# pmi_extension_2k13.net
KiCad netlist of a schematic drawn in EAGLE
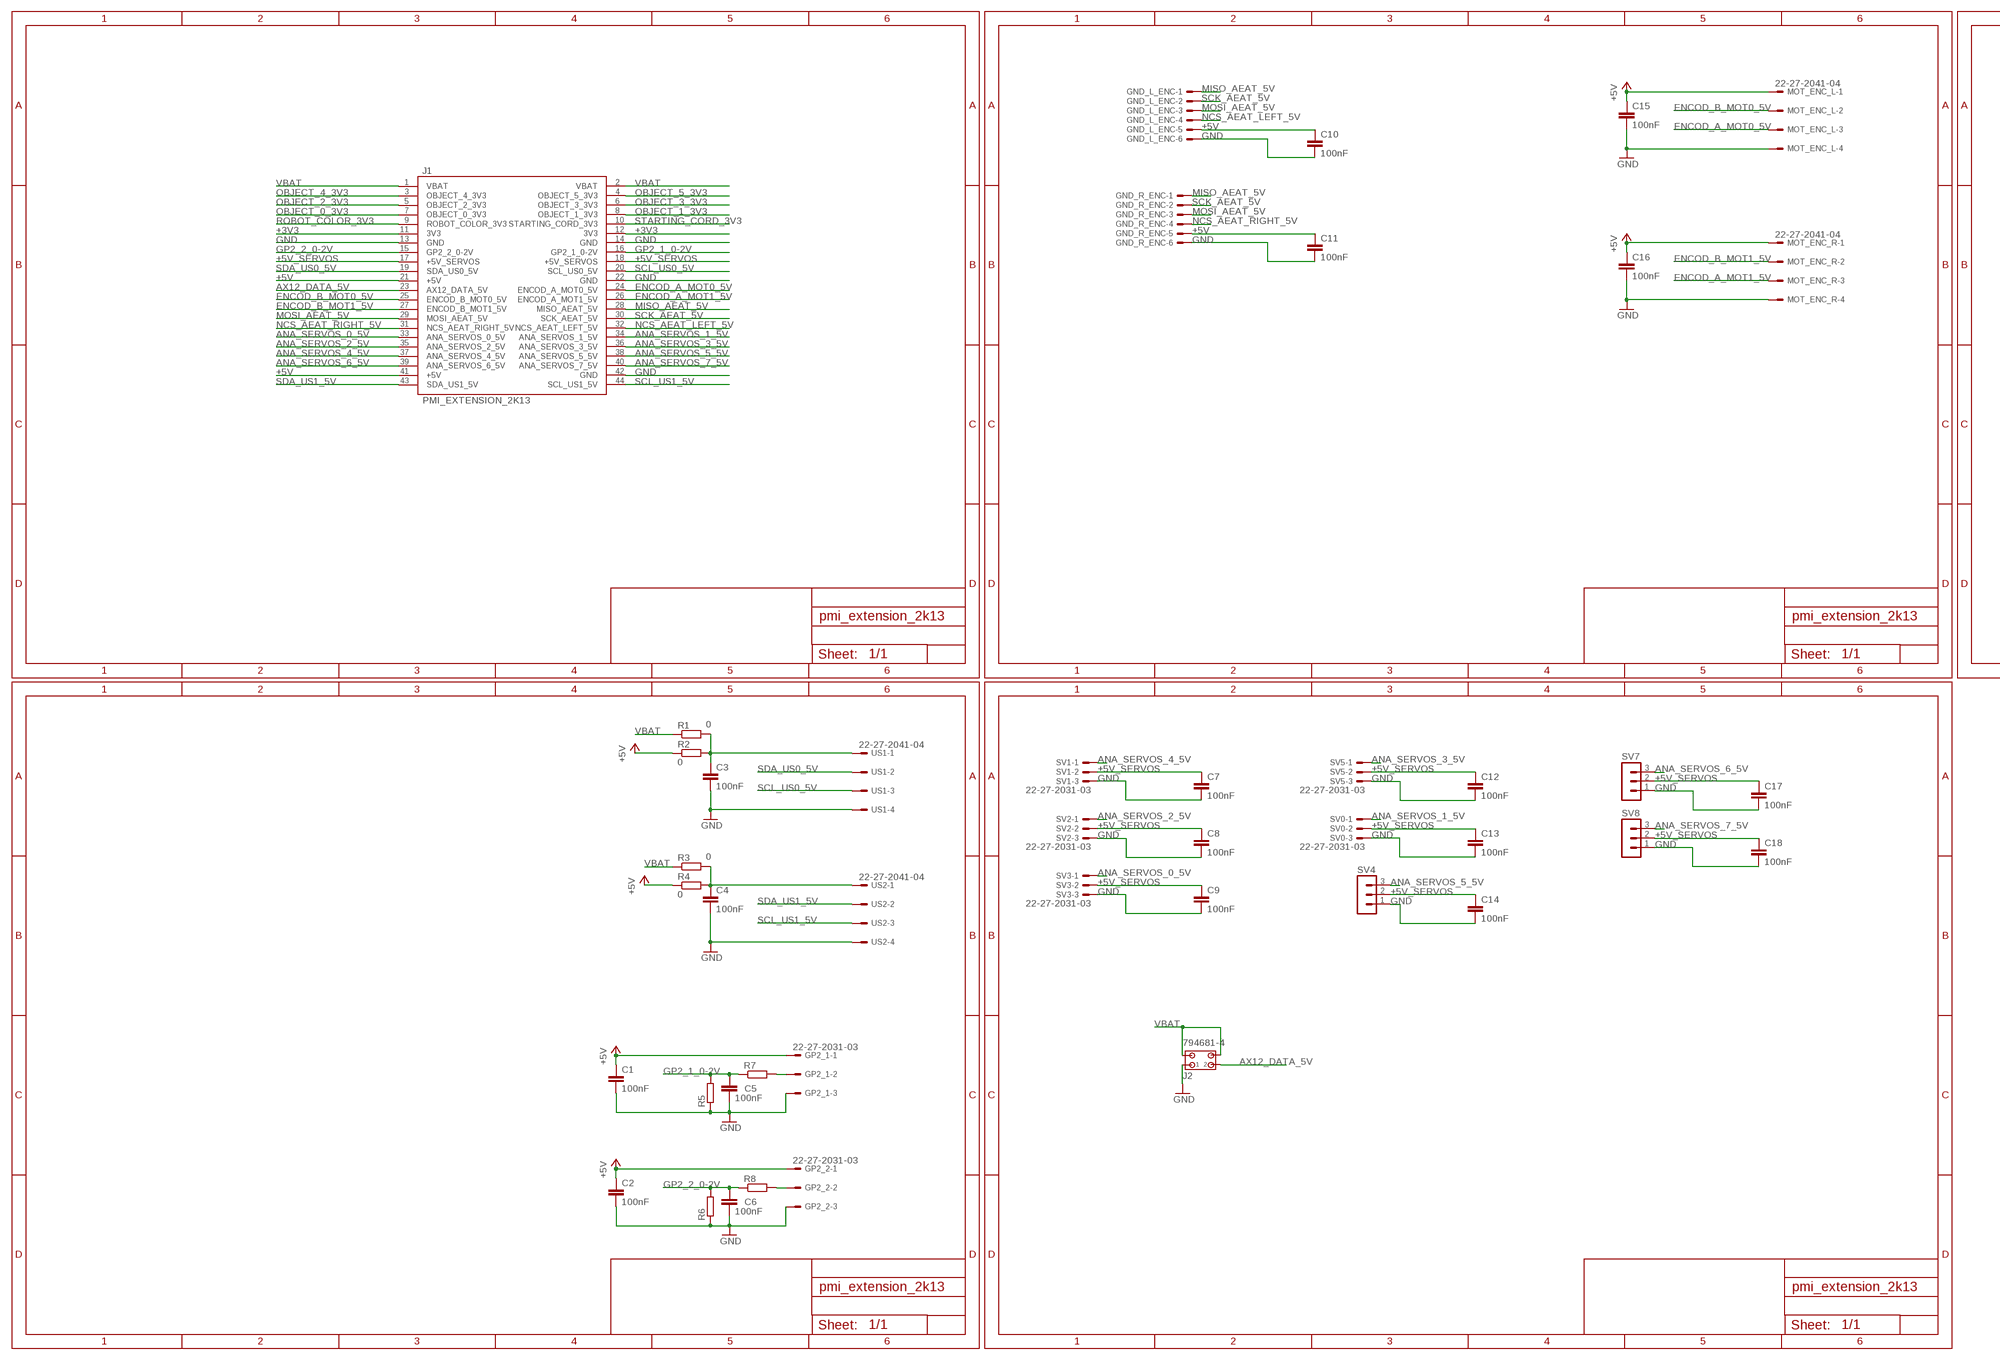
[diagram p0: schematic, sheet 1, part 1 of 2]
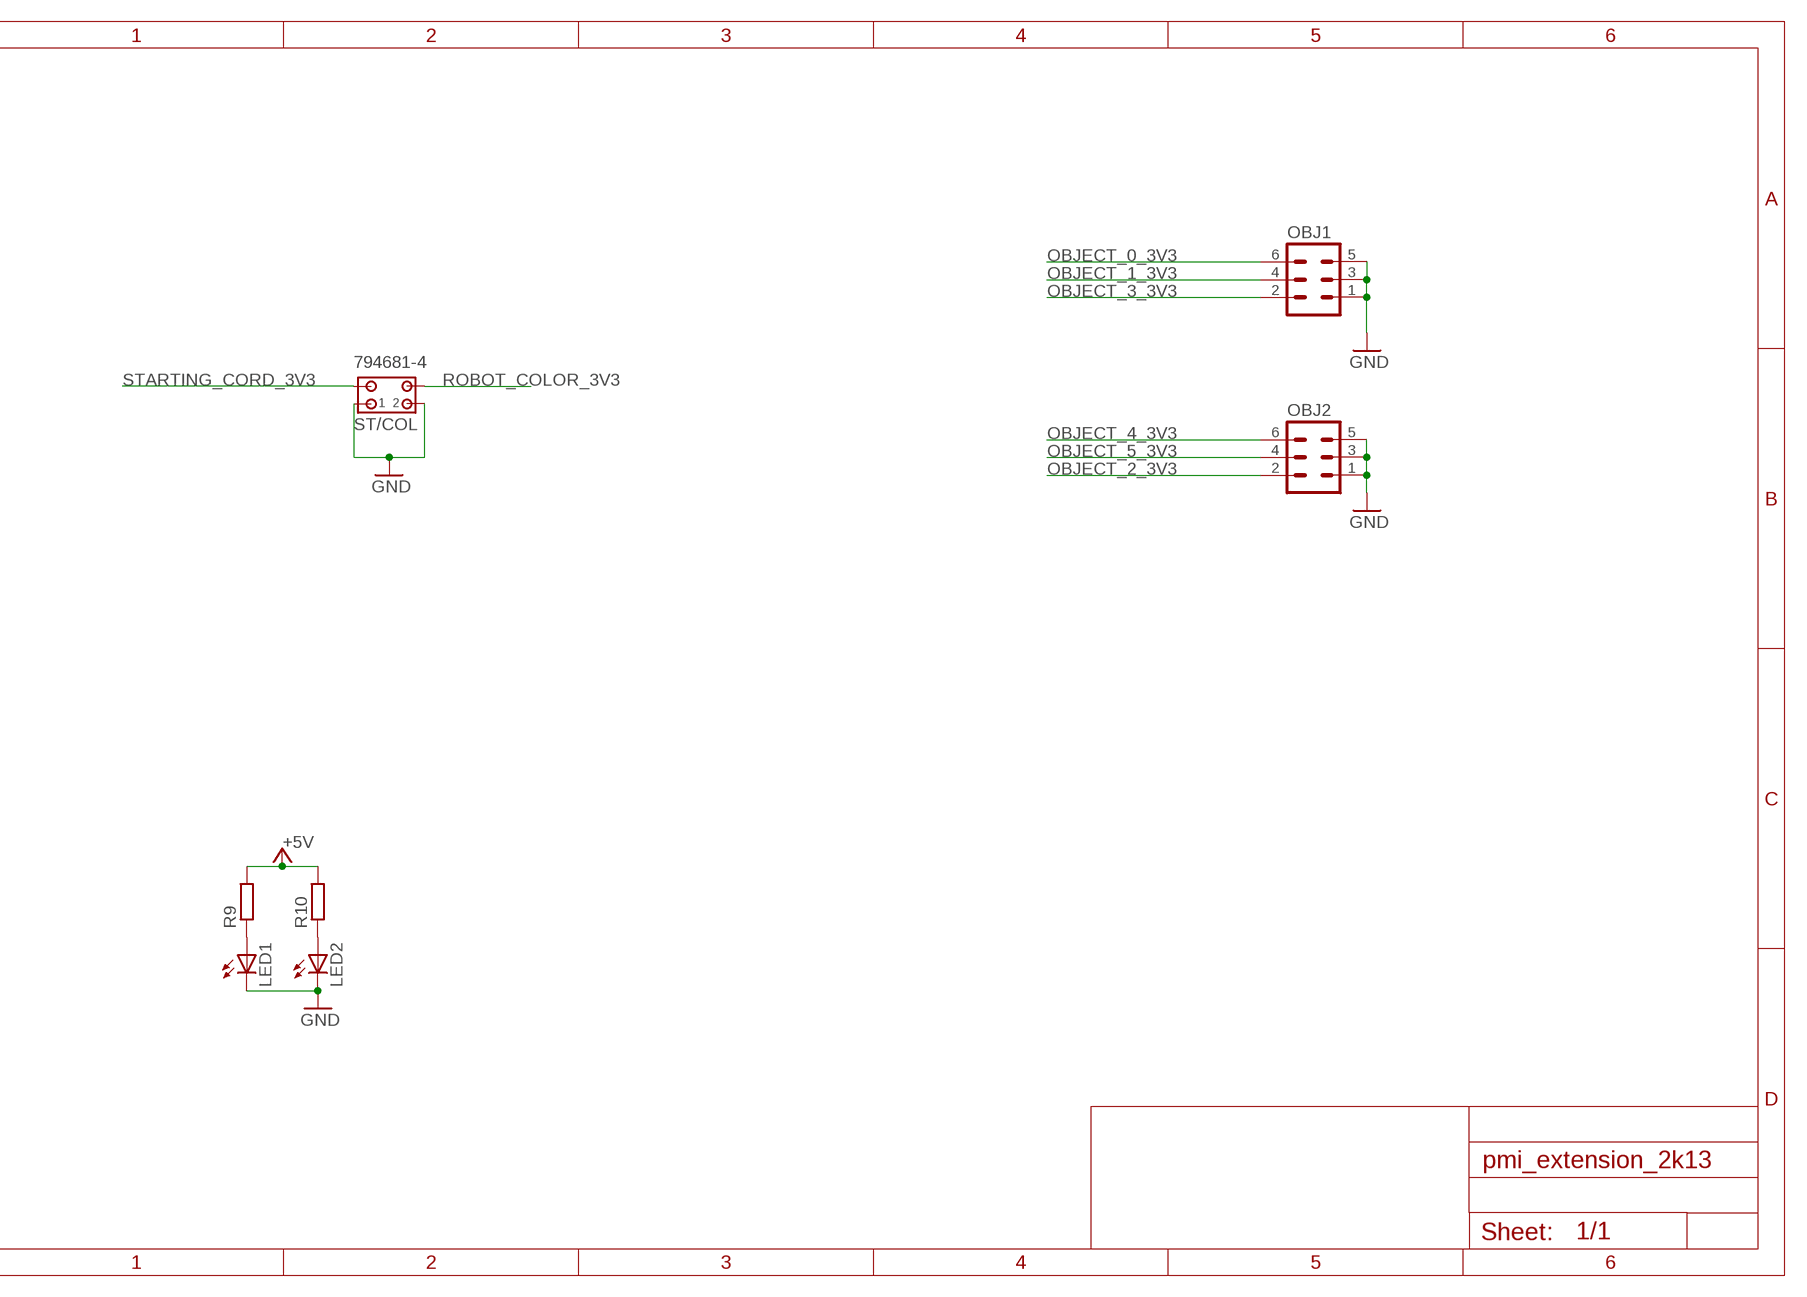
[diagram p1: schematic, sheet 1, part 2 of 2]

(export (version "E")
  (design (tool "Eeschema 10.0.6"))
  (components
    (comp (ref "C1")
      (value "100nF")
      (footprint "eagle-import:C0603")
      (libsource (lib "eagle-import") (part "C-EUC0603"))
    )
    (comp (ref "C2")
      (value "100nF")
      (footprint "eagle-import:C0603")
      (libsource (lib "eagle-import") (part "C-EUC0603"))
    )
    (comp (ref "C3")
      (value "100nF")
      (footprint "eagle-import:C0603")
      (libsource (lib "eagle-import") (part "C-EUC0603"))
    )
    (comp (ref "C4")
      (value "100nF")
      (footprint "eagle-import:C0603")
      (libsource (lib "eagle-import") (part "C-EUC0603"))
    )
    (comp (ref "C5")
      (value "100nF")
      (footprint "eagle-import:C0603")
      (libsource (lib "eagle-import") (part "C-EUC0603"))
    )
    (comp (ref "C6")
      (value "100nF")
      (footprint "eagle-import:C0603")
      (libsource (lib "eagle-import") (part "C-EUC0603"))
    )
    (comp (ref "C7")
      (value "100nF")
      (footprint "eagle-import:C0805")
      (libsource (lib "eagle-import") (part "C-EUC0805"))
    )
    (comp (ref "C8")
      (value "100nF")
      (footprint "eagle-import:C0805")
      (libsource (lib "eagle-import") (part "C-EUC0805"))
    )
    (comp (ref "C9")
      (value "100nF")
      (footprint "eagle-import:C0805")
      (libsource (lib "eagle-import") (part "C-EUC0805"))
    )
    (comp (ref "C10")
      (value "100nF")
      (footprint "eagle-import:C0603")
      (libsource (lib "eagle-import") (part "C-EUC0603"))
    )
    (comp (ref "C11")
      (value "100nF")
      (footprint "eagle-import:C0603")
      (libsource (lib "eagle-import") (part "C-EUC0603"))
    )
    (comp (ref "C12")
      (value "100nF")
      (footprint "eagle-import:C0805")
      (libsource (lib "eagle-import") (part "C-EUC0805"))
    )
    (comp (ref "C13")
      (value "100nF")
      (footprint "eagle-import:C0805")
      (libsource (lib "eagle-import") (part "C-EUC0805"))
    )
    (comp (ref "C14")
      (value "100nF")
      (footprint "eagle-import:C0603")
      (libsource (lib "eagle-import") (part "C-EUC0603"))
    )
    (comp (ref "C15")
      (value "100nF")
      (footprint "eagle-import:C0603")
      (libsource (lib "eagle-import") (part "C-EUC0603"))
    )
    (comp (ref "C16")
      (value "100nF")
      (footprint "eagle-import:C0603")
      (libsource (lib "eagle-import") (part "C-EUC0603"))
    )
    (comp (ref "C17")
      (value "100nF")
      (footprint "eagle-import:C0603")
      (libsource (lib "eagle-import") (part "C-EUC0603"))
    )
    (comp (ref "C18")
      (value "100nF")
      (footprint "eagle-import:C0603")
      (libsource (lib "eagle-import") (part "C-EUC0603"))
    )
    (comp (ref "GND_L_ENC")
      (value "22-23-2061")
      (footprint "eagle-import:22-23-2061")
      (fields (field (name "MF") "MOLEX"))
      (libsource (lib "eagle-import") (part "22-23-2061"))
    )
    (comp (ref "GND_R_ENC")
      (value "22-23-2061")
      (footprint "eagle-import:22-23-2061")
      (fields (field (name "MF") "MOLEX"))
      (libsource (lib "eagle-import") (part "22-23-2061"))
    )
    (comp (ref "GP2_1")
      (value "22-27-2031-03")
      (footprint "eagle-import:6410-03")
      (libsource (lib "eagle-import") (part "22-?-0327-2031"))
    )
    (comp (ref "GP2_2")
      (value "22-27-2031-03")
      (footprint "eagle-import:6410-03")
      (libsource (lib "eagle-import") (part "22-?-0327-2031"))
    )
    (comp (ref "J1")
      (value "PMI_EXTENSION_2K13")
      (footprint "eagle-import:HEADER_2X22")
      (libsource (lib "eagle-import") (part "PMI_EXTENSION_2K13"))
    )
    (comp (ref "J2")
      (value "794681-4")
      (footprint "eagle-import:794681-4")
      (libsource (lib "eagle-import") (part "794681-4"))
    )
    (comp (ref "LED1")
      (value "LED3MM")
      (footprint "eagle-import:LED3MM")
      (libsource (lib "eagle-import") (part "LED3MM"))
    )
    (comp (ref "LED2")
      (value "LED3MM")
      (footprint "eagle-import:LED3MM")
      (libsource (lib "eagle-import") (part "LED3MM"))
    )
    (comp (ref "MOT_ENC_L")
      (value "22-27-2041-04")
      (footprint "eagle-import:6410-04")
      (libsource (lib "eagle-import") (part "22-?-0427-2041"))
    )
    (comp (ref "MOT_ENC_R")
      (value "22-27-2041-04")
      (footprint "eagle-import:6410-04")
      (libsource (lib "eagle-import") (part "22-?-0427-2041"))
    )
    (comp (ref "OBJ1")
      (value "MA03-2")
      (footprint "eagle-import:MA03-2")
      (libsource (lib "eagle-import") (part "MA03-2"))
    )
    (comp (ref "OBJ2")
      (value "MA03-2")
      (footprint "eagle-import:MA03-2")
      (libsource (lib "eagle-import") (part "MA03-2"))
    )
    (comp (ref "R1")
      (value "0")
      (footprint "eagle-import:R0603")
      (libsource (lib "eagle-import") (part "R-EU_R0603"))
    )
    (comp (ref "R2")
      (value "0")
      (footprint "eagle-import:R0603")
      (libsource (lib "eagle-import") (part "R-EU_R0603"))
    )
    (comp (ref "R3")
      (value "0")
      (footprint "eagle-import:R0603")
      (libsource (lib "eagle-import") (part "R-EU_R0603"))
    )
    (comp (ref "R4")
      (value "0")
      (footprint "eagle-import:R0603")
      (libsource (lib "eagle-import") (part "R-EU_R0603"))
    )
    (comp (ref "R5")
      (value "R-EU_R0603")
      (footprint "eagle-import:R0603")
      (libsource (lib "eagle-import") (part "R-EU_R0603"))
    )
    (comp (ref "R6")
      (value "R-EU_R0603")
      (footprint "eagle-import:R0603")
      (libsource (lib "eagle-import") (part "R-EU_R0603"))
    )
    (comp (ref "R7")
      (value "R-EU_R0603")
      (footprint "eagle-import:R0603")
      (libsource (lib "eagle-import") (part "R-EU_R0603"))
    )
    (comp (ref "R8")
      (value "R-EU_R0603")
      (footprint "eagle-import:R0603")
      (libsource (lib "eagle-import") (part "R-EU_R0603"))
    )
    (comp (ref "R9")
      (value "R-EU_R0603")
      (footprint "eagle-import:R0603")
      (libsource (lib "eagle-import") (part "R-EU_R0603"))
    )
    (comp (ref "R10")
      (value "R-EU_R0603")
      (footprint "eagle-import:R0603")
      (libsource (lib "eagle-import") (part "R-EU_R0603"))
    )
    (comp (ref "ST/COL")
      (value "794681-4")
      (footprint "eagle-import:794681-4")
      (libsource (lib "eagle-import") (part "794681-4"))
    )
    (comp (ref "SV0")
      (value "22-27-2031-03")
      (footprint "eagle-import:6410-03")
      (libsource (lib "eagle-import") (part "22-?-0327-2031"))
    )
    (comp (ref "SV1")
      (value "22-27-2031-03")
      (footprint "eagle-import:6410-03")
      (libsource (lib "eagle-import") (part "22-?-0327-2031"))
    )
    (comp (ref "SV2")
      (value "22-27-2031-03")
      (footprint "eagle-import:6410-03")
      (libsource (lib "eagle-import") (part "22-?-0327-2031"))
    )
    (comp (ref "SV3")
      (value "22-27-2031-03")
      (footprint "eagle-import:6410-03")
      (libsource (lib "eagle-import") (part "22-?-0327-2031"))
    )
    (comp (ref "SV4")
      (value "MA03-1")
      (footprint "eagle-import:MA03-1")
      (fields (field (name "OC_FARNELL") "unknown") (field (name "OC_NEWARK") "unknown"))
      (libsource (lib "eagle-import") (part "MA03-1"))
    )
    (comp (ref "SV5")
      (value "22-27-2031-03")
      (footprint "eagle-import:6410-03")
      (libsource (lib "eagle-import") (part "22-?-0327-2031"))
    )
    (comp (ref "SV7")
      (value "MA03-1")
      (footprint "eagle-import:MA03-1")
      (libsource (lib "eagle-import") (part "MA03-1"))
    )
    (comp (ref "SV8")
      (value "MA03-1")
      (footprint "eagle-import:MA03-1")
      (libsource (lib "eagle-import") (part "MA03-1"))
    )
    (comp (ref "US1")
      (value "22-27-2041-04")
      (footprint "eagle-import:6410-04")
      (libsource (lib "eagle-import") (part "22-?-0427-2041"))
    )
    (comp (ref "US2")
      (value "22-27-2041-04")
      (footprint "eagle-import:6410-04")
      (libsource (lib "eagle-import") (part "22-?-0427-2041"))
    )
  )
  (nets
    (net (code "1") (name "+5V") (class "Default")
      (node (ref "C1") (pin "1") (pinfunction "1_1") (pintype "passive"))
      (node (ref "C10") (pin "1") (pinfunction "1_1") (pintype "passive"))
      (node (ref "C11") (pin "1") (pinfunction "1_1") (pintype "passive"))
      (node (ref "C15") (pin "1") (pinfunction "1_1") (pintype "passive"))
      (node (ref "C16") (pin "1") (pinfunction "1_1") (pintype "passive"))
      (node (ref "C2") (pin "1") (pinfunction "1_1") (pintype "passive"))
      (node (ref "GND_L_ENC") (pin "5") (pinfunction "S_5") (pintype "passive"))
      (node (ref "GND_R_ENC") (pin "5") (pinfunction "S_5") (pintype "passive"))
      (node (ref "GP2_1") (pin "1") (pinfunction "S_1") (pintype "passive"))
      (node (ref "GP2_2") (pin "1") (pinfunction "S_1") (pintype "passive"))
      (node (ref "J1") (pin "21") (pinfunction "+5V_21") (pintype "bidirectional"))
      (node (ref "J1") (pin "41") (pinfunction "+5V_41") (pintype "bidirectional"))
      (node (ref "MOT_ENC_L") (pin "1") (pinfunction "S_1") (pintype "passive"))
      (node (ref "MOT_ENC_R") (pin "1") (pinfunction "S_1") (pintype "passive"))
      (node (ref "R10") (pin "2") (pinfunction "2_2") (pintype "passive"))
      (node (ref "R2") (pin "1") (pinfunction "1_1") (pintype "passive"))
      (node (ref "R4") (pin "1") (pinfunction "1_1") (pintype "passive"))
      (node (ref "R9") (pin "2") (pinfunction "2_2") (pintype "passive"))
    )
    (net (code "2") (name "/+3V3") (class "Default")
      (node (ref "J1") (pin "11") (pinfunction "3V3_11") (pintype "bidirectional"))
      (node (ref "J1") (pin "12") (pinfunction "3V3_12") (pintype "bidirectional"))
    )
    (net (code "3") (name "/+5V_SERVOS") (class "Default")
      (node (ref "C12") (pin "1") (pinfunction "1_1") (pintype "passive"))
      (node (ref "C13") (pin "1") (pinfunction "1_1") (pintype "passive"))
      (node (ref "C14") (pin "1") (pinfunction "1_1") (pintype "passive"))
      (node (ref "C17") (pin "1") (pinfunction "1_1") (pintype "passive"))
      (node (ref "C18") (pin "1") (pinfunction "1_1") (pintype "passive"))
      (node (ref "C7") (pin "1") (pinfunction "1_1") (pintype "passive"))
      (node (ref "C8") (pin "1") (pinfunction "1_1") (pintype "passive"))
      (node (ref "C9") (pin "1") (pinfunction "1_1") (pintype "passive"))
      (node (ref "J1") (pin "17") (pinfunction "+5V_SERVOS_17") (pintype "bidirectional"))
      (node (ref "J1") (pin "18") (pinfunction "+5V_SERVOS_18") (pintype "bidirectional"))
      (node (ref "SV0") (pin "2") (pinfunction "S_2") (pintype "passive"))
      (node (ref "SV1") (pin "2") (pinfunction "S_2") (pintype "passive"))
      (node (ref "SV2") (pin "2") (pinfunction "S_2") (pintype "passive"))
      (node (ref "SV3") (pin "2") (pinfunction "S_2") (pintype "passive"))
      (node (ref "SV4") (pin "2") (pinfunction "2_2") (pintype "passive"))
      (node (ref "SV5") (pin "2") (pinfunction "S_2") (pintype "passive"))
      (node (ref "SV7") (pin "2") (pinfunction "2_2") (pintype "passive"))
      (node (ref "SV8") (pin "2") (pinfunction "2_2") (pintype "passive"))
    )
    (net (code "4") (name "/ANA_SERVOS_0_5V") (class "Default")
      (node (ref "J1") (pin "33") (pinfunction "ANA_SERVOS_0_5V_33") (pintype "bidirectional"))
      (node (ref "SV3") (pin "1") (pinfunction "S_1") (pintype "passive"))
    )
    (net (code "5") (name "/ANA_SERVOS_1_5V") (class "Default")
      (node (ref "J1") (pin "34") (pinfunction "ANA_SERVOS_1_5V_34") (pintype "bidirectional"))
      (node (ref "SV0") (pin "1") (pinfunction "S_1") (pintype "passive"))
    )
    (net (code "6") (name "/ANA_SERVOS_2_5V") (class "Default")
      (node (ref "J1") (pin "35") (pinfunction "ANA_SERVOS_2_5V_35") (pintype "bidirectional"))
      (node (ref "SV2") (pin "1") (pinfunction "S_1") (pintype "passive"))
    )
    (net (code "7") (name "/ANA_SERVOS_3_5V") (class "Default")
      (node (ref "J1") (pin "36") (pinfunction "ANA_SERVOS_3_5V_36") (pintype "bidirectional"))
      (node (ref "SV5") (pin "1") (pinfunction "S_1") (pintype "passive"))
    )
    (net (code "8") (name "/ANA_SERVOS_4_5V") (class "Default")
      (node (ref "J1") (pin "37") (pinfunction "ANA_SERVOS_4_5V_37") (pintype "bidirectional"))
      (node (ref "SV1") (pin "1") (pinfunction "S_1") (pintype "passive"))
    )
    (net (code "9") (name "/ANA_SERVOS_5_5V") (class "Default")
      (node (ref "J1") (pin "38") (pinfunction "ANA_SERVOS_5_5V_38") (pintype "bidirectional"))
      (node (ref "SV4") (pin "3") (pinfunction "3_3") (pintype "passive"))
    )
    (net (code "10") (name "/ANA_SERVOS_6_5V") (class "Default")
      (node (ref "J1") (pin "39") (pinfunction "ANA_SERVOS_6_5V_39") (pintype "bidirectional"))
      (node (ref "SV7") (pin "3") (pinfunction "3_3") (pintype "passive"))
    )
    (net (code "11") (name "/ANA_SERVOS_7_5V") (class "Default")
      (node (ref "J1") (pin "40") (pinfunction "ANA_SERVOS_7_5V_40") (pintype "bidirectional"))
      (node (ref "SV8") (pin "3") (pinfunction "3_3") (pintype "passive"))
    )
    (net (code "12") (name "/AX12_DATA_5V") (class "Default")
      (node (ref "J1") (pin "23") (pinfunction "AX12_DATA_5V_23") (pintype "bidirectional"))
      (node (ref "J2") (pin "2") (pinfunction "2_2") (pintype "passive"))
    )
    (net (code "13") (name "/ENCOD_A_MOT0_5V") (class "Default")
      (node (ref "J1") (pin "24") (pinfunction "ENCOD_A_MOT0_5V_24") (pintype "bidirectional"))
      (node (ref "MOT_ENC_L") (pin "3") (pinfunction "S_3") (pintype "passive"))
    )
    (net (code "14") (name "/ENCOD_A_MOT1_5V") (class "Default")
      (node (ref "J1") (pin "26") (pinfunction "ENCOD_A_MOT1_5V_26") (pintype "bidirectional"))
      (node (ref "MOT_ENC_R") (pin "3") (pinfunction "S_3") (pintype "passive"))
    )
    (net (code "15") (name "/ENCOD_B_MOT0_5V") (class "Default")
      (node (ref "J1") (pin "25") (pinfunction "ENCOD_B_MOT0_5V_25") (pintype "bidirectional"))
      (node (ref "MOT_ENC_L") (pin "2") (pinfunction "S_2") (pintype "passive"))
    )
    (net (code "16") (name "/ENCOD_B_MOT1_5V") (class "Default")
      (node (ref "J1") (pin "27") (pinfunction "ENCOD_B_MOT1_5V_27") (pintype "bidirectional"))
      (node (ref "MOT_ENC_R") (pin "2") (pinfunction "S_2") (pintype "passive"))
    )
    (net (code "17") (name "/GP2_1_0-2V") (class "Default")
      (node (ref "C5") (pin "1") (pinfunction "1_1") (pintype "passive"))
      (node (ref "J1") (pin "16") (pinfunction "GP2_1_0-2V_16") (pintype "bidirectional"))
      (node (ref "R5") (pin "2") (pinfunction "2_2") (pintype "passive"))
      (node (ref "R7") (pin "1") (pinfunction "1_1") (pintype "passive"))
    )
    (net (code "18") (name "/GP2_2_0-2V") (class "Default")
      (node (ref "C6") (pin "1") (pinfunction "1_1") (pintype "passive"))
      (node (ref "J1") (pin "15") (pinfunction "GP2_2_0-2V_15") (pintype "bidirectional"))
      (node (ref "R6") (pin "2") (pinfunction "2_2") (pintype "passive"))
      (node (ref "R8") (pin "1") (pinfunction "1_1") (pintype "passive"))
    )
    (net (code "19") (name "/MISO_AEAT_5V") (class "Default")
      (node (ref "GND_L_ENC") (pin "1") (pinfunction "S_1") (pintype "passive"))
      (node (ref "GND_R_ENC") (pin "1") (pinfunction "S_1") (pintype "passive"))
      (node (ref "J1") (pin "28") (pinfunction "MISO_AEAT_5V_28") (pintype "bidirectional"))
    )
    (net (code "20") (name "/MOSI_AEAT_5V") (class "Default")
      (node (ref "GND_L_ENC") (pin "3") (pinfunction "S_3") (pintype "passive"))
      (node (ref "GND_R_ENC") (pin "3") (pinfunction "S_3") (pintype "passive"))
      (node (ref "J1") (pin "29") (pinfunction "MOSI_AEAT_5V_29") (pintype "bidirectional"))
    )
    (net (code "21") (name "/NCS_AEAT_LEFT_5V") (class "Default")
      (node (ref "GND_L_ENC") (pin "4") (pinfunction "S_4") (pintype "passive"))
      (node (ref "J1") (pin "32") (pinfunction "NCS_AEAT_LEFT_5V_32") (pintype "bidirectional"))
    )
    (net (code "22") (name "/NCS_AEAT_RIGHT_5V") (class "Default")
      (node (ref "GND_R_ENC") (pin "4") (pinfunction "S_4") (pintype "passive"))
      (node (ref "J1") (pin "31") (pinfunction "NCS_AEAT_RIGHT_5V_31") (pintype "bidirectional"))
    )
    (net (code "23") (name "/OBJECT_0_3V3") (class "Default")
      (node (ref "J1") (pin "7") (pinfunction "OBJECT_0_3V3_7") (pintype "bidirectional"))
      (node (ref "OBJ1") (pin "6") (pinfunction "6_6") (pintype "passive"))
    )
    (net (code "24") (name "/OBJECT_1_3V3") (class "Default")
      (node (ref "J1") (pin "8") (pinfunction "OBJECT_1_3V3_8") (pintype "bidirectional"))
      (node (ref "OBJ1") (pin "4") (pinfunction "4_4") (pintype "passive"))
    )
    (net (code "25") (name "/OBJECT_2_3V3") (class "Default")
      (node (ref "J1") (pin "5") (pinfunction "OBJECT_2_3V3_5") (pintype "bidirectional"))
      (node (ref "OBJ2") (pin "2") (pinfunction "2_2") (pintype "passive"))
    )
    (net (code "26") (name "/OBJECT_3_3V3") (class "Default")
      (node (ref "J1") (pin "6") (pinfunction "OBJECT_3_3V3_6") (pintype "bidirectional"))
      (node (ref "OBJ1") (pin "2") (pinfunction "2_2") (pintype "passive"))
    )
    (net (code "27") (name "/OBJECT_4_3V3") (class "Default")
      (node (ref "J1") (pin "3") (pinfunction "OBJECT_4_3V3_3") (pintype "bidirectional"))
      (node (ref "OBJ2") (pin "6") (pinfunction "6_6") (pintype "passive"))
    )
    (net (code "28") (name "/OBJECT_5_3V3") (class "Default")
      (node (ref "J1") (pin "4") (pinfunction "OBJECT_5_3V3_4") (pintype "bidirectional"))
      (node (ref "OBJ2") (pin "4") (pinfunction "4_4") (pintype "passive"))
    )
    (net (code "29") (name "/ROBOT_COLOR_3V3") (class "Default")
      (node (ref "J1") (pin "9") (pinfunction "ROBOT_COLOR_3V3_9") (pintype "bidirectional"))
      (node (ref "ST/COL") (pin "4") (pinfunction "4_4") (pintype "passive"))
    )
    (net (code "30") (name "/SCK_AEAT_5V") (class "Default")
      (node (ref "GND_L_ENC") (pin "2") (pinfunction "S_2") (pintype "passive"))
      (node (ref "GND_R_ENC") (pin "2") (pinfunction "S_2") (pintype "passive"))
      (node (ref "J1") (pin "30") (pinfunction "SCK_AEAT_5V_30") (pintype "bidirectional"))
    )
    (net (code "31") (name "/SCL_US0_5V") (class "Default")
      (node (ref "J1") (pin "20") (pinfunction "SCL_US0_5V_20") (pintype "bidirectional"))
      (node (ref "US1") (pin "3") (pinfunction "S_3") (pintype "passive"))
    )
    (net (code "32") (name "/SCL_US1_5V") (class "Default")
      (node (ref "J1") (pin "44") (pinfunction "SCL_US1_5V_44") (pintype "bidirectional"))
      (node (ref "US2") (pin "3") (pinfunction "S_3") (pintype "passive"))
    )
    (net (code "33") (name "/SDA_US0_5V") (class "Default")
      (node (ref "J1") (pin "19") (pinfunction "SDA_US0_5V_19") (pintype "bidirectional"))
      (node (ref "US1") (pin "2") (pinfunction "S_2") (pintype "passive"))
    )
    (net (code "34") (name "/SDA_US1_5V") (class "Default")
      (node (ref "J1") (pin "43") (pinfunction "SDA_US1_5V_43") (pintype "bidirectional"))
      (node (ref "US2") (pin "2") (pinfunction "S_2") (pintype "passive"))
    )
    (net (code "35") (name "/STARTING_CORD_3V3") (class "Default")
      (node (ref "J1") (pin "10") (pinfunction "STARTING_CORD_3V3_10") (pintype "bidirectional"))
      (node (ref "ST/COL") (pin "3") (pinfunction "3_3") (pintype "passive"))
    )
    (net (code "36") (name "/VBAT") (class "Default")
      (node (ref "J1") (pin "1") (pinfunction "VBAT_1") (pintype "bidirectional"))
      (node (ref "J1") (pin "2") (pinfunction "VBAT_2") (pintype "bidirectional"))
      (node (ref "J2") (pin "3") (pinfunction "3_3") (pintype "passive"))
      (node (ref "J2") (pin "4") (pinfunction "4_4") (pintype "passive"))
      (node (ref "R1") (pin "1") (pinfunction "1_1") (pintype "passive"))
      (node (ref "R3") (pin "1") (pinfunction "1_1") (pintype "passive"))
    )
    (net (code "37") (name "GND") (class "Default")
      (node (ref "C1") (pin "2") (pinfunction "2_2") (pintype "passive"))
      (node (ref "C10") (pin "2") (pinfunction "2_2") (pintype "passive"))
      (node (ref "C11") (pin "2") (pinfunction "2_2") (pintype "passive"))
      (node (ref "C12") (pin "2") (pinfunction "2_2") (pintype "passive"))
      (node (ref "C13") (pin "2") (pinfunction "2_2") (pintype "passive"))
      (node (ref "C14") (pin "2") (pinfunction "2_2") (pintype "passive"))
      (node (ref "C15") (pin "2") (pinfunction "2_2") (pintype "passive"))
      (node (ref "C16") (pin "2") (pinfunction "2_2") (pintype "passive"))
      (node (ref "C17") (pin "2") (pinfunction "2_2") (pintype "passive"))
      (node (ref "C18") (pin "2") (pinfunction "2_2") (pintype "passive"))
      (node (ref "C2") (pin "2") (pinfunction "2_2") (pintype "passive"))
      (node (ref "C3") (pin "2") (pinfunction "2_2") (pintype "passive"))
      (node (ref "C4") (pin "2") (pinfunction "2_2") (pintype "passive"))
      (node (ref "C5") (pin "2") (pinfunction "2_2") (pintype "passive"))
      (node (ref "C6") (pin "2") (pinfunction "2_2") (pintype "passive"))
      (node (ref "C7") (pin "2") (pinfunction "2_2") (pintype "passive"))
      (node (ref "C8") (pin "2") (pinfunction "2_2") (pintype "passive"))
      (node (ref "C9") (pin "2") (pinfunction "2_2") (pintype "passive"))
      (node (ref "GND_L_ENC") (pin "6") (pinfunction "S_6") (pintype "passive"))
      (node (ref "GND_R_ENC") (pin "6") (pinfunction "S_6") (pintype "passive"))
      (node (ref "GP2_1") (pin "3") (pinfunction "S_3") (pintype "passive"))
      (node (ref "GP2_2") (pin "3") (pinfunction "S_3") (pintype "passive"))
      (node (ref "J1") (pin "13") (pinfunction "GND_13") (pintype "bidirectional"))
      (node (ref "J1") (pin "14") (pinfunction "GND_14") (pintype "bidirectional"))
      (node (ref "J1") (pin "22") (pinfunction "GND_22") (pintype "bidirectional"))
      (node (ref "J1") (pin "42") (pinfunction "GND_42") (pintype "bidirectional"))
      (node (ref "J2") (pin "1") (pinfunction "1_1") (pintype "passive"))
      (node (ref "LED1") (pin "K") (pinfunction "C_K") (pintype "passive"))
      (node (ref "LED2") (pin "K") (pinfunction "C_K") (pintype "passive"))
      (node (ref "MOT_ENC_L") (pin "4") (pinfunction "S_4") (pintype "passive"))
      (node (ref "MOT_ENC_R") (pin "4") (pinfunction "S_4") (pintype "passive"))
      (node (ref "OBJ1") (pin "1") (pinfunction "1_1") (pintype "passive"))
      (node (ref "OBJ1") (pin "3") (pinfunction "3_3") (pintype "passive"))
      (node (ref "OBJ1") (pin "5") (pinfunction "5_5") (pintype "passive"))
      (node (ref "OBJ2") (pin "1") (pinfunction "1_1") (pintype "passive"))
      (node (ref "OBJ2") (pin "3") (pinfunction "3_3") (pintype "passive"))
      (node (ref "OBJ2") (pin "5") (pinfunction "5_5") (pintype "passive"))
      (node (ref "R5") (pin "1") (pinfunction "1_1") (pintype "passive"))
      (node (ref "R6") (pin "1") (pinfunction "1_1") (pintype "passive"))
      (node (ref "ST/COL") (pin "1") (pinfunction "1_1") (pintype "passive"))
      (node (ref "ST/COL") (pin "2") (pinfunction "2_2") (pintype "passive"))
      (node (ref "SV0") (pin "3") (pinfunction "S_3") (pintype "passive"))
      (node (ref "SV1") (pin "3") (pinfunction "S_3") (pintype "passive"))
      (node (ref "SV2") (pin "3") (pinfunction "S_3") (pintype "passive"))
      (node (ref "SV3") (pin "3") (pinfunction "S_3") (pintype "passive"))
      (node (ref "SV4") (pin "1") (pinfunction "1_1") (pintype "passive"))
      (node (ref "SV5") (pin "3") (pinfunction "S_3") (pintype "passive"))
      (node (ref "SV7") (pin "1") (pinfunction "1_1") (pintype "passive"))
      (node (ref "SV8") (pin "1") (pinfunction "1_1") (pintype "passive"))
      (node (ref "US1") (pin "4") (pinfunction "S_4") (pintype "passive"))
      (node (ref "US2") (pin "4") (pinfunction "S_4") (pintype "passive"))
    )
    (net (code "38") (name "Net-(GP2_1B-S)") (class "Default")
      (node (ref "GP2_1") (pin "2") (pinfunction "S_2") (pintype "passive"))
      (node (ref "R7") (pin "2") (pinfunction "2_2") (pintype "passive"))
    )
    (net (code "39") (name "Net-(GP2_2B-S)") (class "Default")
      (node (ref "GP2_2") (pin "2") (pinfunction "S_2") (pintype "passive"))
      (node (ref "R8") (pin "2") (pinfunction "2_2") (pintype "passive"))
    )
    (net (code "40") (name "Net-(LED1-PadA)") (class "Default")
      (node (ref "LED1") (pin "A") (pinfunction "A_A") (pintype "passive"))
      (node (ref "R9") (pin "1") (pinfunction "1_1") (pintype "passive"))
    )
    (net (code "41") (name "Net-(LED2-PadA)") (class "Default")
      (node (ref "LED2") (pin "A") (pinfunction "A_A") (pintype "passive"))
      (node (ref "R10") (pin "1") (pinfunction "1_1") (pintype "passive"))
    )
    (net (code "42") (name "Net-(US1A-S)") (class "Default")
      (node (ref "C3") (pin "1") (pinfunction "1_1") (pintype "passive"))
      (node (ref "R1") (pin "2") (pinfunction "2_2") (pintype "passive"))
      (node (ref "R2") (pin "2") (pinfunction "2_2") (pintype "passive"))
      (node (ref "US1") (pin "1") (pinfunction "S_1") (pintype "passive"))
    )
    (net (code "43") (name "Net-(US2A-S)") (class "Default")
      (node (ref "C4") (pin "1") (pinfunction "1_1") (pintype "passive"))
      (node (ref "R3") (pin "2") (pinfunction "2_2") (pintype "passive"))
      (node (ref "R4") (pin "2") (pinfunction "2_2") (pintype "passive"))
      (node (ref "US2") (pin "1") (pinfunction "S_1") (pintype "passive"))
    )
  )
)
